# Power_Main.net
KiCad netlist of a schematic drawn in Altium Designer
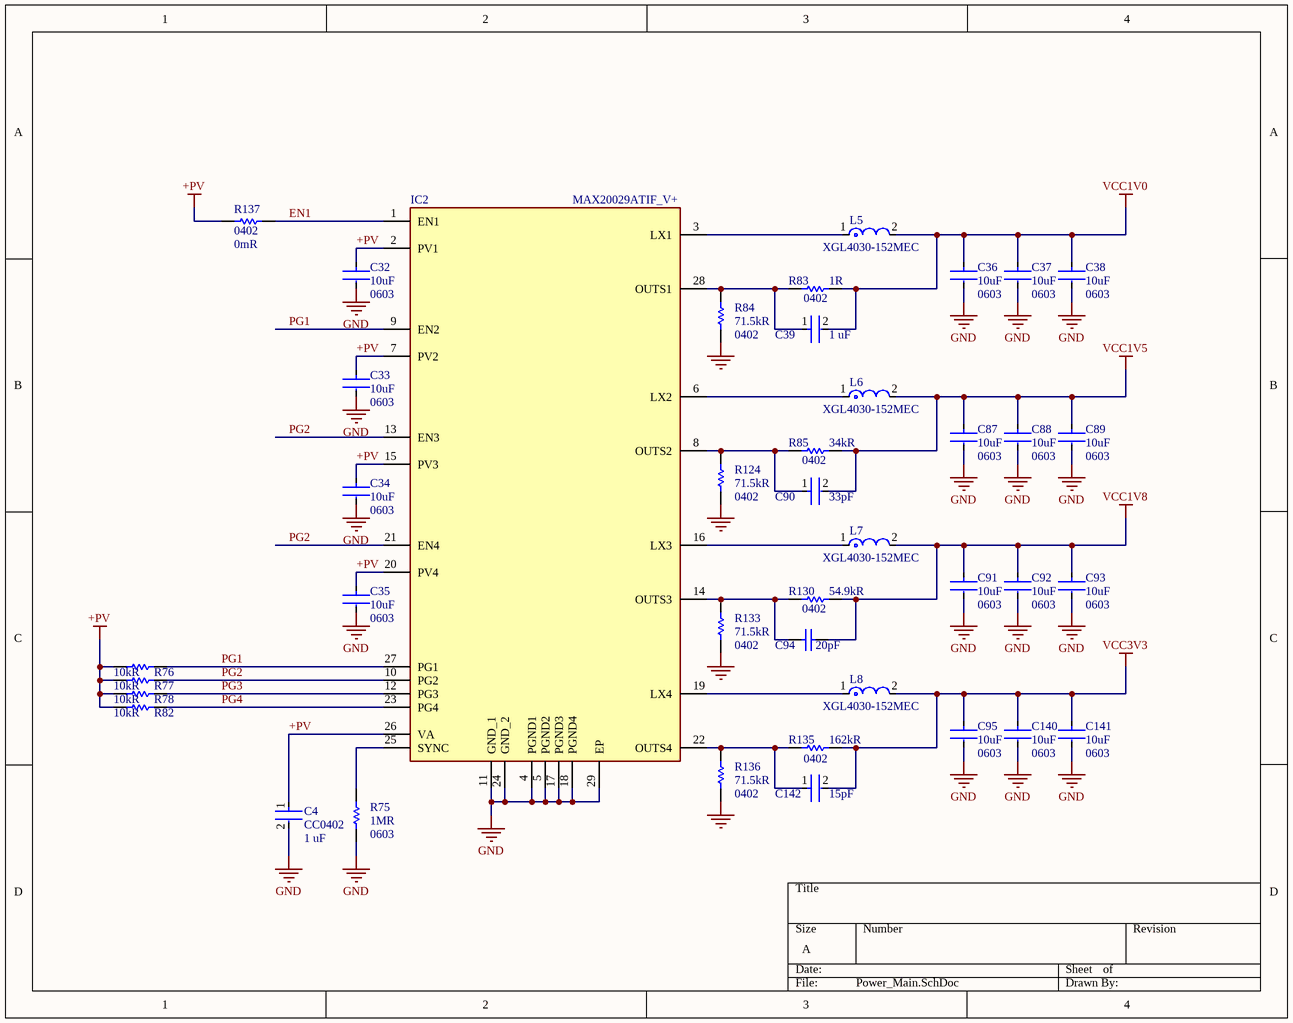
[diagram p0: Power_Main.SchDoc]

(export (version "E")
  (design (tool "Eeschema 10.0.6"))
  (components
    (comp (ref "C4")
      (value "1 uF")
      (footprint "FP-CC0402-MFG")
      (description "CC0402 1 uF X5R 10.00% 6.3 V")
      (fields (field (name "MANUFACTURER") "YAGEO") (field (name "PACKAGE") "CC0402"))
      (libsource (lib "Altium Content Vault") (part "11868f565c42a9108669ba33697ecf6"))
    )
    (comp (ref "C32")
      (value "10uF")
      (footprint "FP-GRM188-0_1-e0_2_0_55-IPC_A")
      (description "Chip Multilayer Ceramic Capacitors for General Purpose, 0603, 10uF, X5R, 15%, 20%, 6.3V")
      (fields
        (field (name "CASE/PACKAGE") "0603")
        (field (name "VOLTAGE") "6.3V")
        (field (name "TOLERANCE") "20%")
      )
      (libsource (lib "Altium Content Vault") (part "02cd4be3c70576c341d710602a673aa"))
    )
    (comp (ref "C33")
      (value "10uF")
      (footprint "FP-GRM188-0_1-e0_2_0_55-IPC_A")
      (description "Chip Multilayer Ceramic Capacitors for General Purpose, 0603, 10uF, X5R, 15%, 20%, 6.3V")
      (fields
        (field (name "CASE/PACKAGE") "0603")
        (field (name "VOLTAGE") "6.3V")
        (field (name "TOLERANCE") "20%")
      )
      (libsource (lib "Altium Content Vault") (part "02cd4be3c70576c341d710602a673aa"))
    )
    (comp (ref "C34")
      (value "10uF")
      (footprint "FP-GRM188-0_1-e0_2_0_55-IPC_A")
      (description "Chip Multilayer Ceramic Capacitors for General Purpose, 0603, 10uF, X5R, 15%, 20%, 6.3V")
      (fields
        (field (name "CASE/PACKAGE") "0603")
        (field (name "VOLTAGE") "6.3V")
        (field (name "TOLERANCE") "20%")
      )
      (libsource (lib "Altium Content Vault") (part "02cd4be3c70576c341d710602a673aa"))
    )
    (comp (ref "C35")
      (value "10uF")
      (footprint "FP-GRM188-0_1-e0_2_0_55-IPC_A")
      (description "Chip Multilayer Ceramic Capacitors for General Purpose, 0603, 10uF, X5R, 15%, 20%, 6.3V")
      (fields
        (field (name "CASE/PACKAGE") "0603")
        (field (name "VOLTAGE") "6.3V")
        (field (name "TOLERANCE") "20%")
      )
      (libsource (lib "Altium Content Vault") (part "02cd4be3c70576c341d710602a673aa"))
    )
    (comp (ref "C36")
      (value "10uF")
      (footprint "FP-GRM188-0_1-e0_2_0_55-IPC_A")
      (description "Chip Multilayer Ceramic Capacitors for General Purpose, 0603, 10uF, X5R, 15%, 20%, 6.3V")
      (fields
        (field (name "CASE/PACKAGE") "0603")
        (field (name "VOLTAGE") "6.3V")
        (field (name "TOLERANCE") "20%")
      )
      (libsource (lib "Altium Content Vault") (part "02cd4be3c70576c341d710602a673aa"))
    )
    (comp (ref "C37")
      (value "10uF")
      (footprint "FP-GRM188-0_1-e0_2_0_55-IPC_A")
      (description "Chip Multilayer Ceramic Capacitors for General Purpose, 0603, 10uF, X5R, 15%, 20%, 6.3V")
      (fields
        (field (name "CASE/PACKAGE") "0603")
        (field (name "VOLTAGE") "6.3V")
        (field (name "TOLERANCE") "20%")
      )
      (libsource (lib "Altium Content Vault") (part "02cd4be3c70576c341d710602a673aa"))
    )
    (comp (ref "C38")
      (value "10uF")
      (footprint "FP-GRM188-0_1-e0_2_0_55-IPC_A")
      (description "Chip Multilayer Ceramic Capacitors for General Purpose, 0603, 10uF, X5R, 15%, 20%, 6.3V")
      (fields
        (field (name "CASE/PACKAGE") "0603")
        (field (name "VOLTAGE") "6.3V")
        (field (name "TOLERANCE") "20%")
      )
      (libsource (lib "Altium Content Vault") (part "02cd4be3c70576c341d710602a673aa"))
    )
    (comp (ref "C39")
      (value "1 uF")
      (footprint "FP-CC0402-MFG")
      (description "CC0402 1 uF X5R 10.00% 6.3 V")
      (fields (field (name "MANUFACTURER") "YAGEO"))
      (libsource (lib "Altium Content Vault") (part "11868f565c42a9108669ba33697ecf6"))
    )
    (comp (ref "C87")
      (value "10uF")
      (footprint "FP-GRM188-0_1-e0_2_0_55-IPC_A")
      (description "Chip Multilayer Ceramic Capacitors for General Purpose, 0603, 10uF, X5R, 15%, 20%, 6.3V")
      (fields
        (field (name "CASE/PACKAGE") "0603")
        (field (name "VOLTAGE") "6.3V")
        (field (name "TOLERANCE") "20%")
      )
      (libsource (lib "Altium Content Vault") (part "02cd4be3c70576c341d710602a673aa"))
    )
    (comp (ref "C88")
      (value "10uF")
      (footprint "FP-GRM188-0_1-e0_2_0_55-IPC_A")
      (description "Chip Multilayer Ceramic Capacitors for General Purpose, 0603, 10uF, X5R, 15%, 20%, 6.3V")
      (fields
        (field (name "CASE/PACKAGE") "0603")
        (field (name "VOLTAGE") "6.3V")
        (field (name "TOLERANCE") "20%")
      )
      (libsource (lib "Altium Content Vault") (part "02cd4be3c70576c341d710602a673aa"))
    )
    (comp (ref "C89")
      (value "10uF")
      (footprint "FP-GRM188-0_1-e0_2_0_55-IPC_A")
      (description "Chip Multilayer Ceramic Capacitors for General Purpose, 0603, 10uF, X5R, 15%, 20%, 6.3V")
      (fields
        (field (name "CASE/PACKAGE") "0603")
        (field (name "VOLTAGE") "6.3V")
        (field (name "TOLERANCE") "20%")
      )
      (libsource (lib "Altium Content Vault") (part "02cd4be3c70576c341d710602a673aa"))
    )
    (comp (ref "C90")
      (value "04025A330JAT2A")
      (footprint "FP-0402-L_1_0_1-W_0_5_0_1-IPC_A")
      (description "General Purpose Ceramic Capacitor, 0402, 33pF, 5%, C0G, 30ppm/°C, 50V")
      (fields
        (field (name "TOLERANCE") "5%")
        (field (name "VOLTAGE") "50V")
        (field (name "CAPACITANCE") "33pF")
      )
      (libsource (lib "Altium Content Vault") (part "b4654b650e69147ec39a6b967a45e02"))
    )
    (comp (ref "C91")
      (value "10uF")
      (footprint "FP-GRM188-0_1-e0_2_0_55-IPC_A")
      (description "Chip Multilayer Ceramic Capacitors for General Purpose, 0603, 10uF, X5R, 15%, 20%, 6.3V")
      (fields
        (field (name "CASE/PACKAGE") "0603")
        (field (name "VOLTAGE") "6.3V")
        (field (name "TOLERANCE") "20%")
      )
      (libsource (lib "Altium Content Vault") (part "02cd4be3c70576c341d710602a673aa"))
    )
    (comp (ref "C92")
      (value "10uF")
      (footprint "FP-GRM188-0_1-e0_2_0_55-IPC_A")
      (description "Chip Multilayer Ceramic Capacitors for General Purpose, 0603, 10uF, X5R, 15%, 20%, 6.3V")
      (fields
        (field (name "CASE/PACKAGE") "0603")
        (field (name "VOLTAGE") "6.3V")
        (field (name "TOLERANCE") "20%")
      )
      (libsource (lib "Altium Content Vault") (part "02cd4be3c70576c341d710602a673aa"))
    )
    (comp (ref "C93")
      (value "10uF")
      (footprint "FP-GRM188-0_1-e0_2_0_55-IPC_A")
      (description "Chip Multilayer Ceramic Capacitors for General Purpose, 0603, 10uF, X5R, 15%, 20%, 6.3V")
      (fields
        (field (name "CASE/PACKAGE") "0603")
        (field (name "VOLTAGE") "6.3V")
        (field (name "TOLERANCE") "20%")
      )
      (libsource (lib "Altium Content Vault") (part "02cd4be3c70576c341d710602a673aa"))
    )
    (comp (ref "C94")
      (value "20pF")
      (footprint "CAPC1005X56X25NL10T15")
      (description "0402 50V C0G 20pF 5% multilayer ceramic capacitor")
      (fields
        (field (name "PART NUMBER") "04025A200JAT2A")
        (field (name "MANUFACTURER") "AVX Interconnect / Elco")
      )
      (libsource (lib "Altium Content Vault") (part "CAP"))
    )
    (comp (ref "C95")
      (value "10uF")
      (footprint "FP-GRM188-0_1-e0_2_0_55-IPC_A")
      (description "Chip Multilayer Ceramic Capacitors for General Purpose, 0603, 10uF, X5R, 15%, 20%, 6.3V")
      (fields
        (field (name "CASE/PACKAGE") "0603")
        (field (name "VOLTAGE") "6.3V")
        (field (name "TOLERANCE") "20%")
      )
      (libsource (lib "Altium Content Vault") (part "02cd4be3c70576c341d710602a673aa"))
    )
    (comp (ref "C140")
      (value "10uF")
      (footprint "FP-GRM188-0_1-e0_2_0_55-IPC_A")
      (description "Chip Multilayer Ceramic Capacitors for General Purpose, 0603, 10uF, X5R, 15%, 20%, 6.3V")
      (fields
        (field (name "CASE/PACKAGE") "0603")
        (field (name "VOLTAGE") "6.3V")
        (field (name "TOLERANCE") "20%")
      )
      (libsource (lib "Altium Content Vault") (part "02cd4be3c70576c341d710602a673aa"))
    )
    (comp (ref "C141")
      (value "10uF")
      (footprint "FP-GRM188-0_1-e0_2_0_55-IPC_A")
      (description "Chip Multilayer Ceramic Capacitors for General Purpose, 0603, 10uF, X5R, 15%, 20%, 6.3V")
      (fields
        (field (name "CASE/PACKAGE") "0603")
        (field (name "VOLTAGE") "6.3V")
        (field (name "TOLERANCE") "20%")
      )
      (libsource (lib "Altium Content Vault") (part "02cd4be3c70576c341d710602a673aa"))
    )
    (comp (ref "C142")
      (value "15pF")
      (footprint "FP-0402-L_1_0_1-W_0_5_0_1-IPC_A")
      (description "General Purpose Ceramic Capacitor, 0402, 15pF, 5%, C0G, 30ppm/°C, 50V")
      (fields (field (name "VOLTAGE") "50V") (field (name "TOLERANCE") "5%"))
      (libsource (lib "Altium Content Vault") (part "b4654b650e69147ec39a6b967a45e02"))
    )
    (comp (ref "IC2")
      (value "MAX20029ATIF_V+")
      (footprint "SamacSys:QFN50P500X500X80-29N")
      (description "Switching Voltage Regulators Updated 4-ch PMIC")
      (fields (field (name "MANUFACTURER_PART_NUMBER") "MAX20029ATIF/V+"))
      (libsource (lib "SamacSys") (part "MAX20029ATIF_V+"))
    )
    (comp (ref "L5")
      (value "XGL4030-152MEC")
      (footprint "FP-XGL4030-MFG")
      (description "SHIELDED POWER INDUCTORS, 1.5UH")
      (libsource (lib "Altium Content Vault") (part "4cc4b267dca4c8e51f7102f422741d8"))
    )
    (comp (ref "L6")
      (value "XGL4030-152MEC")
      (footprint "FP-XGL4030-MFG")
      (description "SHIELDED POWER INDUCTORS, 1.5UH")
      (libsource (lib "Altium Content Vault") (part "4cc4b267dca4c8e51f7102f422741d8"))
    )
    (comp (ref "L7")
      (value "XGL4030-152MEC")
      (footprint "FP-XGL4030-MFG")
      (description "SHIELDED POWER INDUCTORS, 1.5UH")
      (libsource (lib "Altium Content Vault") (part "4cc4b267dca4c8e51f7102f422741d8"))
    )
    (comp (ref "L8")
      (value "XGL4030-152MEC")
      (footprint "FP-XGL4030-MFG")
      (description "SHIELDED POWER INDUCTORS, 1.5UH")
      (libsource (lib "Altium Content Vault") (part "4cc4b267dca4c8e51f7102f422741d8"))
    )
    (comp (ref "R75")
      (value "1MR")
      (footprint "RESC1608X55X25LL10T15")
      (description "Chip Resistor, 1 MOhm, +/- 1%, 100 mW, -55 to 155 degC, 0603 (1608 Metric), RoHS, Tape and Reel")
      (fields
        (field (name "TOLERANCE") "20%")
        (field (name "PACKAGEREFERENCE") "0603")
        (field (name "MANUFACTURER") "Yageo")
      )
      (libsource (lib "Altium Content Vault") (part "RES-2"))
    )
    (comp (ref "R76")
      (value "10kR")
      (footprint "RESC1005X40X25LL05T10")
      (description "10K 0402 1% 1/16W +-100PPM")
      (fields (field (name "PART NUMBER") "RC0402FR-0710KL") (field (name "MANUFACTURER") "Yageo / Phycomp"))
      (libsource (lib "Altium Content Vault") (part "RES"))
    )
    (comp (ref "R77")
      (value "10kR")
      (footprint "RESC1005X40X25LL05T10")
      (description "10K 0402 1% 1/16W +-100PPM")
      (fields (field (name "PART NUMBER") "RC0402FR-0710KL") (field (name "MANUFACTURER") "Yageo / Phycomp"))
      (libsource (lib "Altium Content Vault") (part "RES"))
    )
    (comp (ref "R78")
      (value "10kR")
      (footprint "RESC1005X40X25LL05T10")
      (description "10K 0402 1% 1/16W +-100PPM")
      (fields (field (name "PART NUMBER") "RC0402FR-0710KL") (field (name "MANUFACTURER") "Yageo / Phycomp"))
      (libsource (lib "Altium Content Vault") (part "RES"))
    )
    (comp (ref "R82")
      (value "10kR")
      (footprint "RESC1005X40X25LL05T10")
      (description "10K 0402 1% 1/16W +-100PPM")
      (fields (field (name "PART NUMBER") "RC0402FR-0710KL") (field (name "MANUFACTURER") "Yageo / Phycomp"))
      (libsource (lib "Altium Content Vault") (part "RES"))
    )
    (comp (ref "R83")
      (value "1R")
      (footprint "RESC1005X40X25NL05T05")
      (description "Res Thick Film 0402 1 Ohm 5% 1/16W ±200ppm/°C Molded SMD SMD Paper T/R")
      (fields
        (field (name "PART NUMBER") "CRCW04021R00JNED")
        (field (name "MANUFACTURER") "Vishay Dale")
        (field (name "CASE/PACKAGE") "0402")
      )
      (libsource (lib "Altium Content Vault") (part "RES"))
    )
    (comp (ref "R84")
      (value "71.5kR")
      (footprint "RESC1005X40X25LL05T05")
      (description "Res Thick Film 0402 71.5K Ohm 1% 1/10W ±100ppm/°C Molded SMD Punched Carrier T/R")
      (fields
        (field (name "PART NUMBER") "ERJ-2RKF7152X")
        (field (name "MANUFACTURER") "Panasonic")
        (field (name "CASE/PACKAGE") "0402")
      )
      (libsource (lib "Altium Content Vault") (part "RES"))
    )
    (comp (ref "R85")
      (value "34kR")
      (footprint "RESC1005X40X25ML05T05")
      (description "Res Thick Film 0402 34K Ohm 1% 0.063W(1/16W) ±100ppm/C Pad SMD Automotive T/R")
      (fields
        (field (name "MANUFACTURER") "Vishay Dale")
        (field (name "PART NUMBER") "CRCW040234K0FKED")
        (field (name "CASE/PACKAGE") "0402")
      )
      (libsource (lib "Altium Content Vault") (part "RES"))
    )
    (comp (ref "R124")
      (value "71.5kR")
      (footprint "RESC1005X40X25LL05T05")
      (description "Res Thick Film 0402 71.5K Ohm 1% 1/10W ±100ppm/°C Molded SMD Punched Carrier T/R")
      (fields
        (field (name "PART NUMBER") "ERJ-2RKF7152X")
        (field (name "MANUFACTURER") "Panasonic")
        (field (name "CASE/PACKAGE") "0402")
      )
      (libsource (lib "Altium Content Vault") (part "RES"))
    )
    (comp (ref "R130")
      (value "54.9kR")
      (footprint "RESC1005X40X25ML05T05")
      (description "Res Thick Film 0402 54.9K Ohm 1% 1/10W ±100ppm/°C Molded SMD Punched Carrier T/R")
      (fields
        (field (name "MANUFACTURER") "Panasonic")
        (field (name "PART NUMBER") "ERJ-2RKF5492X")
        (field (name "CASE/PACKAGE") "0402")
      )
      (libsource (lib "Altium Content Vault") (part "RES"))
    )
    (comp (ref "R133")
      (value "71.5kR")
      (footprint "RESC1005X40X25LL05T05")
      (description "Res Thick Film 0402 71.5K Ohm 1% 1/10W ±100ppm/°C Molded SMD Punched Carrier T/R")
      (fields
        (field (name "PART NUMBER") "ERJ-2RKF7152X")
        (field (name "MANUFACTURER") "Panasonic")
        (field (name "CASE/PACKAGE") "0402")
      )
      (libsource (lib "Altium Content Vault") (part "RES"))
    )
    (comp (ref "R135")
      (value "162kR")
      (footprint "RESC1005X40X25LL05T05")
      (description "Res Thick Film 0402 162K Ohm 1% 1/10W ±100ppm/°C Molded SMD Punched Carrier T/R")
      (fields
        (field (name "MANUFACTURER") "Panasonic")
        (field (name "PART NUMBER") "ERJ-2RKF1623X")
        (field (name "CASE/PACKAGE") "0402")
      )
      (libsource (lib "Altium Content Vault") (part "RES"))
    )
    (comp (ref "R136")
      (value "71.5kR")
      (footprint "RESC1005X40X25LL05T05")
      (description "Res Thick Film 0402 71.5K Ohm 1% 1/10W ±100ppm/°C Molded SMD Punched Carrier T/R")
      (fields
        (field (name "PART NUMBER") "ERJ-2RKF7152X")
        (field (name "MANUFACTURER") "Panasonic")
        (field (name "CASE/PACKAGE") "0402")
      )
      (libsource (lib "Altium Content Vault") (part "RES"))
    )
    (comp (ref "R137")
      (value "0mR")
      (footprint "RESC1005X40X25NL05T10")
      (fields
        (field (name "MANUFACTURER") "Yageo / Phycomp")
        (field (name "PART NUMBER") "RC0402JR-070RL")
        (field (name "CASE/PACKAGE") "0402")
        (field (name "TOLERANCE") "5%")
      )
      (libsource (lib "Altium Content Vault") (part "RES"))
    )
  )
  (nets
    (net (code "1") (name "+PV") (class "Default")
      (node (ref "C32") (pin "1") (pinfunction "1_1") (pintype "passive"))
      (node (ref "C33") (pin "1") (pinfunction "1_1") (pintype "passive"))
      (node (ref "C34") (pin "1") (pinfunction "1_1") (pintype "passive"))
      (node (ref "C35") (pin "1") (pinfunction "1_1") (pintype "passive"))
      (node (ref "C4") (pin "1") (pinfunction "1_1") (pintype "passive"))
      (node (ref "IC2") (pin "15") (pinfunction "PV3_15") (pintype "passive"))
      (node (ref "IC2") (pin "2") (pinfunction "PV1_2") (pintype "passive"))
      (node (ref "IC2") (pin "20") (pinfunction "PV4_20") (pintype "passive"))
      (node (ref "IC2") (pin "26") (pinfunction "VA_26") (pintype "passive"))
      (node (ref "IC2") (pin "7") (pinfunction "PV2_7") (pintype "passive"))
      (node (ref "R137") (pin "2") (pinfunction "2_2") (pintype "passive"))
      (node (ref "R76") (pin "1") (pinfunction "1_1") (pintype "passive"))
      (node (ref "R77") (pin "1") (pinfunction "1_1") (pintype "passive"))
      (node (ref "R78") (pin "1") (pinfunction "1_1") (pintype "passive"))
      (node (ref "R82") (pin "1") (pinfunction "1_1") (pintype "passive"))
    )
    (net (code "2") (name "/EN1") (class "Default")
      (node (ref "IC2") (pin "1") (pinfunction "EN1_1") (pintype "passive"))
      (node (ref "R137") (pin "1") (pinfunction "1_1") (pintype "passive"))
    )
    (net (code "3") (name "/PG1") (class "Default")
      (node (ref "IC2") (pin "27") (pinfunction "PG1_27") (pintype "passive"))
      (node (ref "IC2") (pin "9") (pinfunction "EN2_9") (pintype "passive"))
      (node (ref "R76") (pin "2") (pinfunction "2_2") (pintype "passive"))
    )
    (net (code "4") (name "/PG2") (class "Default")
      (node (ref "IC2") (pin "10") (pinfunction "PG2_10") (pintype "passive"))
      (node (ref "IC2") (pin "13") (pinfunction "EN3_13") (pintype "passive"))
      (node (ref "IC2") (pin "21") (pinfunction "EN4_21") (pintype "passive"))
      (node (ref "R77") (pin "2") (pinfunction "2_2") (pintype "passive"))
    )
    (net (code "5") (name "/PG3") (class "Default")
      (node (ref "IC2") (pin "12") (pinfunction "PG3_12") (pintype "passive"))
      (node (ref "R78") (pin "2") (pinfunction "2_2") (pintype "passive"))
    )
    (net (code "6") (name "/PG4") (class "Default")
      (node (ref "IC2") (pin "23") (pinfunction "PG4_23") (pintype "passive"))
      (node (ref "R82") (pin "2") (pinfunction "2_2") (pintype "passive"))
    )
    (net (code "7") (name "GND") (class "Default")
      (node (ref "C140") (pin "2") (pinfunction "2_2") (pintype "passive"))
      (node (ref "C141") (pin "2") (pinfunction "2_2") (pintype "passive"))
      (node (ref "C32") (pin "2") (pinfunction "2_2") (pintype "passive"))
      (node (ref "C33") (pin "2") (pinfunction "2_2") (pintype "passive"))
      (node (ref "C34") (pin "2") (pinfunction "2_2") (pintype "passive"))
      (node (ref "C35") (pin "2") (pinfunction "2_2") (pintype "passive"))
      (node (ref "C36") (pin "2") (pinfunction "2_2") (pintype "passive"))
      (node (ref "C37") (pin "2") (pinfunction "2_2") (pintype "passive"))
      (node (ref "C38") (pin "2") (pinfunction "2_2") (pintype "passive"))
      (node (ref "C4") (pin "2") (pinfunction "2_2") (pintype "passive"))
      (node (ref "C87") (pin "2") (pinfunction "2_2") (pintype "passive"))
      (node (ref "C88") (pin "2") (pinfunction "2_2") (pintype "passive"))
      (node (ref "C89") (pin "2") (pinfunction "2_2") (pintype "passive"))
      (node (ref "C91") (pin "2") (pinfunction "2_2") (pintype "passive"))
      (node (ref "C92") (pin "2") (pinfunction "2_2") (pintype "passive"))
      (node (ref "C93") (pin "2") (pinfunction "2_2") (pintype "passive"))
      (node (ref "C95") (pin "2") (pinfunction "2_2") (pintype "passive"))
      (node (ref "IC2") (pin "11") (pinfunction "GND_1_11") (pintype "passive"))
      (node (ref "IC2") (pin "17") (pinfunction "PGND3_17") (pintype "passive"))
      (node (ref "IC2") (pin "18") (pinfunction "PGND4_18") (pintype "passive"))
      (node (ref "IC2") (pin "24") (pinfunction "GND_2_24") (pintype "passive"))
      (node (ref "IC2") (pin "29") (pinfunction "EP_29") (pintype "passive"))
      (node (ref "IC2") (pin "4") (pinfunction "PGND1_4") (pintype "passive"))
      (node (ref "IC2") (pin "5") (pinfunction "PGND2_5") (pintype "passive"))
      (node (ref "R124") (pin "1") (pinfunction "1_1") (pintype "passive"))
      (node (ref "R133") (pin "1") (pinfunction "1_1") (pintype "passive"))
      (node (ref "R136") (pin "1") (pinfunction "1_1") (pintype "passive"))
      (node (ref "R75") (pin "1") (pinfunction "1_1") (pintype "passive"))
      (node (ref "R84") (pin "1") (pinfunction "1_1") (pintype "passive"))
    )
    (net (code "8") (name "Net-(IC2-LX1)") (class "Default")
      (node (ref "IC2") (pin "3") (pinfunction "LX1_3") (pintype "passive"))
      (node (ref "L5") (pin "1") (pinfunction "1_1") (pintype "passive"))
    )
    (net (code "9") (name "Net-(IC2-LX2)") (class "Default")
      (node (ref "IC2") (pin "6") (pinfunction "LX2_6") (pintype "passive"))
      (node (ref "L6") (pin "1") (pinfunction "1_1") (pintype "passive"))
    )
    (net (code "10") (name "Net-(IC2-LX3)") (class "Default")
      (node (ref "IC2") (pin "16") (pinfunction "LX3_16") (pintype "passive"))
      (node (ref "L7") (pin "1") (pinfunction "1_1") (pintype "passive"))
    )
    (net (code "11") (name "Net-(IC2-LX4)") (class "Default")
      (node (ref "IC2") (pin "19") (pinfunction "LX4_19") (pintype "passive"))
      (node (ref "L8") (pin "1") (pinfunction "1_1") (pintype "passive"))
    )
    (net (code "12") (name "Net-(IC2-OUTS1)") (class "Default")
      (node (ref "C39") (pin "1") (pinfunction "1_1") (pintype "passive"))
      (node (ref "IC2") (pin "28") (pinfunction "OUTS1_28") (pintype "passive"))
      (node (ref "R83") (pin "1") (pinfunction "1_1") (pintype "passive"))
      (node (ref "R84") (pin "2") (pinfunction "2_2") (pintype "passive"))
    )
    (net (code "13") (name "Net-(IC2-OUTS2)") (class "Default")
      (node (ref "C90") (pin "1") (pinfunction "1_1") (pintype "passive"))
      (node (ref "IC2") (pin "8") (pinfunction "OUTS2_8") (pintype "passive"))
      (node (ref "R124") (pin "2") (pinfunction "2_2") (pintype "passive"))
      (node (ref "R85") (pin "1") (pinfunction "1_1") (pintype "passive"))
    )
    (net (code "14") (name "Net-(IC2-OUTS3)") (class "Default")
      (node (ref "C94") (pin "1") (pinfunction "1_1") (pintype "passive"))
      (node (ref "IC2") (pin "14") (pinfunction "OUTS3_14") (pintype "passive"))
      (node (ref "R130") (pin "1") (pinfunction "1_1") (pintype "passive"))
      (node (ref "R133") (pin "2") (pinfunction "2_2") (pintype "passive"))
    )
    (net (code "15") (name "Net-(IC2-OUTS4)") (class "Default")
      (node (ref "C142") (pin "1") (pinfunction "1_1") (pintype "passive"))
      (node (ref "IC2") (pin "22") (pinfunction "OUTS4_22") (pintype "passive"))
      (node (ref "R135") (pin "1") (pinfunction "1_1") (pintype "passive"))
      (node (ref "R136") (pin "2") (pinfunction "2_2") (pintype "passive"))
    )
    (net (code "16") (name "Net-(IC2-SYNC)") (class "Default")
      (node (ref "IC2") (pin "25") (pinfunction "SYNC_25") (pintype "passive"))
      (node (ref "R75") (pin "2") (pinfunction "2_2") (pintype "passive"))
    )
    (net (code "17") (name "VCC1V0") (class "Default")
      (node (ref "C36") (pin "1") (pinfunction "1_1") (pintype "passive"))
      (node (ref "C37") (pin "1") (pinfunction "1_1") (pintype "passive"))
      (node (ref "C38") (pin "1") (pinfunction "1_1") (pintype "passive"))
      (node (ref "C39") (pin "2") (pinfunction "2_2") (pintype "passive"))
      (node (ref "L5") (pin "2") (pinfunction "2_2") (pintype "passive"))
      (node (ref "R83") (pin "2") (pinfunction "2_2") (pintype "passive"))
    )
    (net (code "18") (name "VCC1V5") (class "Default")
      (node (ref "C87") (pin "1") (pinfunction "1_1") (pintype "passive"))
      (node (ref "C88") (pin "1") (pinfunction "1_1") (pintype "passive"))
      (node (ref "C89") (pin "1") (pinfunction "1_1") (pintype "passive"))
      (node (ref "C90") (pin "2") (pinfunction "2_2") (pintype "passive"))
      (node (ref "L6") (pin "2") (pinfunction "2_2") (pintype "passive"))
      (node (ref "R85") (pin "2") (pinfunction "2_2") (pintype "passive"))
    )
    (net (code "19") (name "VCC1V8") (class "Default")
      (node (ref "C91") (pin "1") (pinfunction "1_1") (pintype "passive"))
      (node (ref "C92") (pin "1") (pinfunction "1_1") (pintype "passive"))
      (node (ref "C93") (pin "1") (pinfunction "1_1") (pintype "passive"))
      (node (ref "C94") (pin "2") (pinfunction "2_2") (pintype "passive"))
      (node (ref "L7") (pin "2") (pinfunction "2_2") (pintype "passive"))
      (node (ref "R130") (pin "2") (pinfunction "2_2") (pintype "passive"))
    )
    (net (code "20") (name "VCC3V3") (class "Default")
      (node (ref "C140") (pin "1") (pinfunction "1_1") (pintype "passive"))
      (node (ref "C141") (pin "1") (pinfunction "1_1") (pintype "passive"))
      (node (ref "C142") (pin "2") (pinfunction "2_2") (pintype "passive"))
      (node (ref "C95") (pin "1") (pinfunction "1_1") (pintype "passive"))
      (node (ref "L8") (pin "2") (pinfunction "2_2") (pintype "passive"))
      (node (ref "R135") (pin "2") (pinfunction "2_2") (pintype "passive"))
    )
  )
)
